# Zio_Qwiic_to_Grove_Adapter.net
KiCad netlist of a schematic drawn in EAGLE
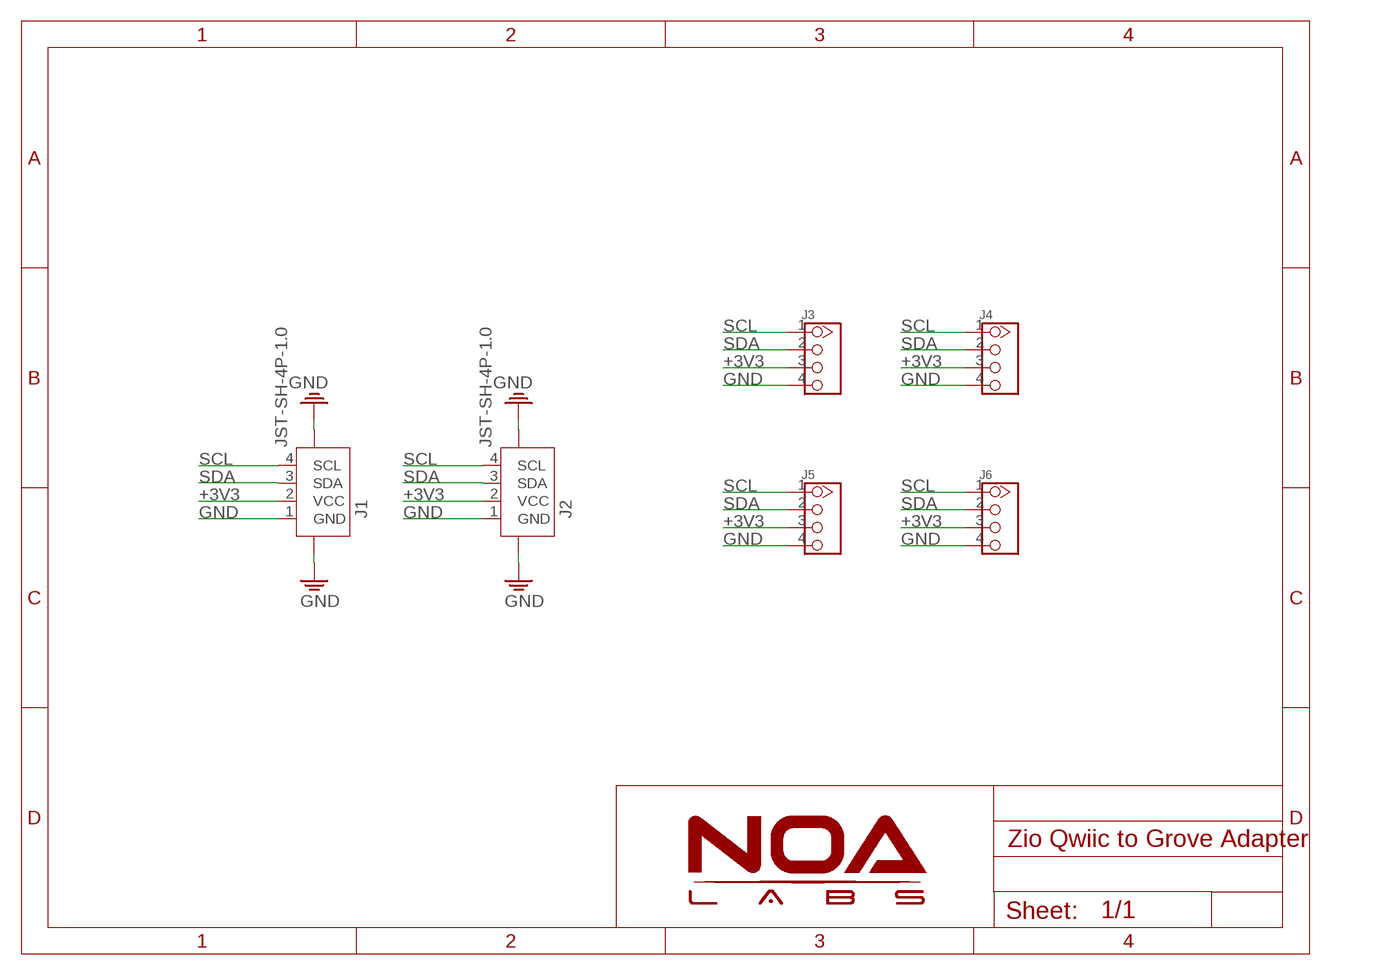
[diagram p0: schematic, sheet 1]

(export (version "E")
  (design (tool "Eeschema 10.0.6"))
  (components
    (comp (ref "J1")
      (value "JST-SH-4P-1.0")
      (footprint "eagle-import:JST-SH-4P")
      (libsource (lib "eagle-import") (part "JST-SH-4P-1.0"))
    )
    (comp (ref "J2")
      (value "JST-SH-4P-1.0")
      (footprint "eagle-import:JST-SH-4P")
      (libsource (lib "eagle-import") (part "JST-SH-4P-1.0"))
    )
    (comp (ref "J3")
      (value "TWIG-4P-2.0-2.0")
      (footprint "eagle-import:4P-2.0")
      (libsource (lib "eagle-import") (part "TWIG-4P-2.0-2.0"))
    )
    (comp (ref "J4")
      (value "TWIG-4P-2.0-2.0")
      (footprint "eagle-import:4P-2.0")
      (libsource (lib "eagle-import") (part "TWIG-4P-2.0-2.0"))
    )
    (comp (ref "J5")
      (value "TWIG-4P-2.0-2.0")
      (footprint "eagle-import:4P-2.0")
      (libsource (lib "eagle-import") (part "TWIG-4P-2.0-2.0"))
    )
    (comp (ref "J6")
      (value "TWIG-4P-2.0-2.0")
      (footprint "eagle-import:4P-2.0")
      (libsource (lib "eagle-import") (part "TWIG-4P-2.0-2.0"))
    )
  )
  (nets
    (net (code "1") (name "/+3V3") (class "Default")
      (node (ref "J1") (pin "2") (pinfunction "VCC_2") (pintype "bidirectional"))
      (node (ref "J2") (pin "2") (pinfunction "VCC_2") (pintype "bidirectional"))
      (node (ref "J3") (pin "3") (pinfunction "3_3") (pintype "bidirectional"))
      (node (ref "J4") (pin "3") (pinfunction "3_3") (pintype "bidirectional"))
      (node (ref "J5") (pin "3") (pinfunction "3_3") (pintype "bidirectional"))
      (node (ref "J6") (pin "3") (pinfunction "3_3") (pintype "bidirectional"))
    )
    (net (code "2") (name "/SCL") (class "Default")
      (node (ref "J1") (pin "4") (pinfunction "SCL_4") (pintype "bidirectional"))
      (node (ref "J2") (pin "4") (pinfunction "SCL_4") (pintype "bidirectional"))
      (node (ref "J3") (pin "1") (pinfunction "1_1") (pintype "bidirectional"))
      (node (ref "J4") (pin "1") (pinfunction "1_1") (pintype "bidirectional"))
      (node (ref "J5") (pin "1") (pinfunction "1_1") (pintype "bidirectional"))
      (node (ref "J6") (pin "1") (pinfunction "1_1") (pintype "bidirectional"))
    )
    (net (code "3") (name "/SDA") (class "Default")
      (node (ref "J1") (pin "3") (pinfunction "SDA_3") (pintype "bidirectional"))
      (node (ref "J2") (pin "3") (pinfunction "SDA_3") (pintype "bidirectional"))
      (node (ref "J3") (pin "2") (pinfunction "2_2") (pintype "bidirectional"))
      (node (ref "J4") (pin "2") (pinfunction "2_2") (pintype "bidirectional"))
      (node (ref "J5") (pin "2") (pinfunction "2_2") (pintype "bidirectional"))
      (node (ref "J6") (pin "2") (pinfunction "2_2") (pintype "bidirectional"))
    )
    (net (code "4") (name "GND") (class "Default")
      (node (ref "J1") (pin "1") (pinfunction "GND_1") (pintype "bidirectional"))
      (node (ref "J1") (pin "NC1") (pinfunction "5_NC1") (pintype "bidirectional"))
      (node (ref "J1") (pin "NC2") (pinfunction "6_NC2") (pintype "bidirectional"))
      (node (ref "J2") (pin "1") (pinfunction "GND_1") (pintype "bidirectional"))
      (node (ref "J2") (pin "NC1") (pinfunction "5_NC1") (pintype "bidirectional"))
      (node (ref "J2") (pin "NC2") (pinfunction "6_NC2") (pintype "bidirectional"))
      (node (ref "J3") (pin "4") (pinfunction "4_4") (pintype "bidirectional"))
      (node (ref "J4") (pin "4") (pinfunction "4_4") (pintype "bidirectional"))
      (node (ref "J5") (pin "4") (pinfunction "4_4") (pintype "bidirectional"))
      (node (ref "J6") (pin "4") (pinfunction "4_4") (pintype "bidirectional"))
    )
  )
)
